# tweeq-FB_Breadboard_v4.net
KiCad netlist of a schematic drawn in EAGLE
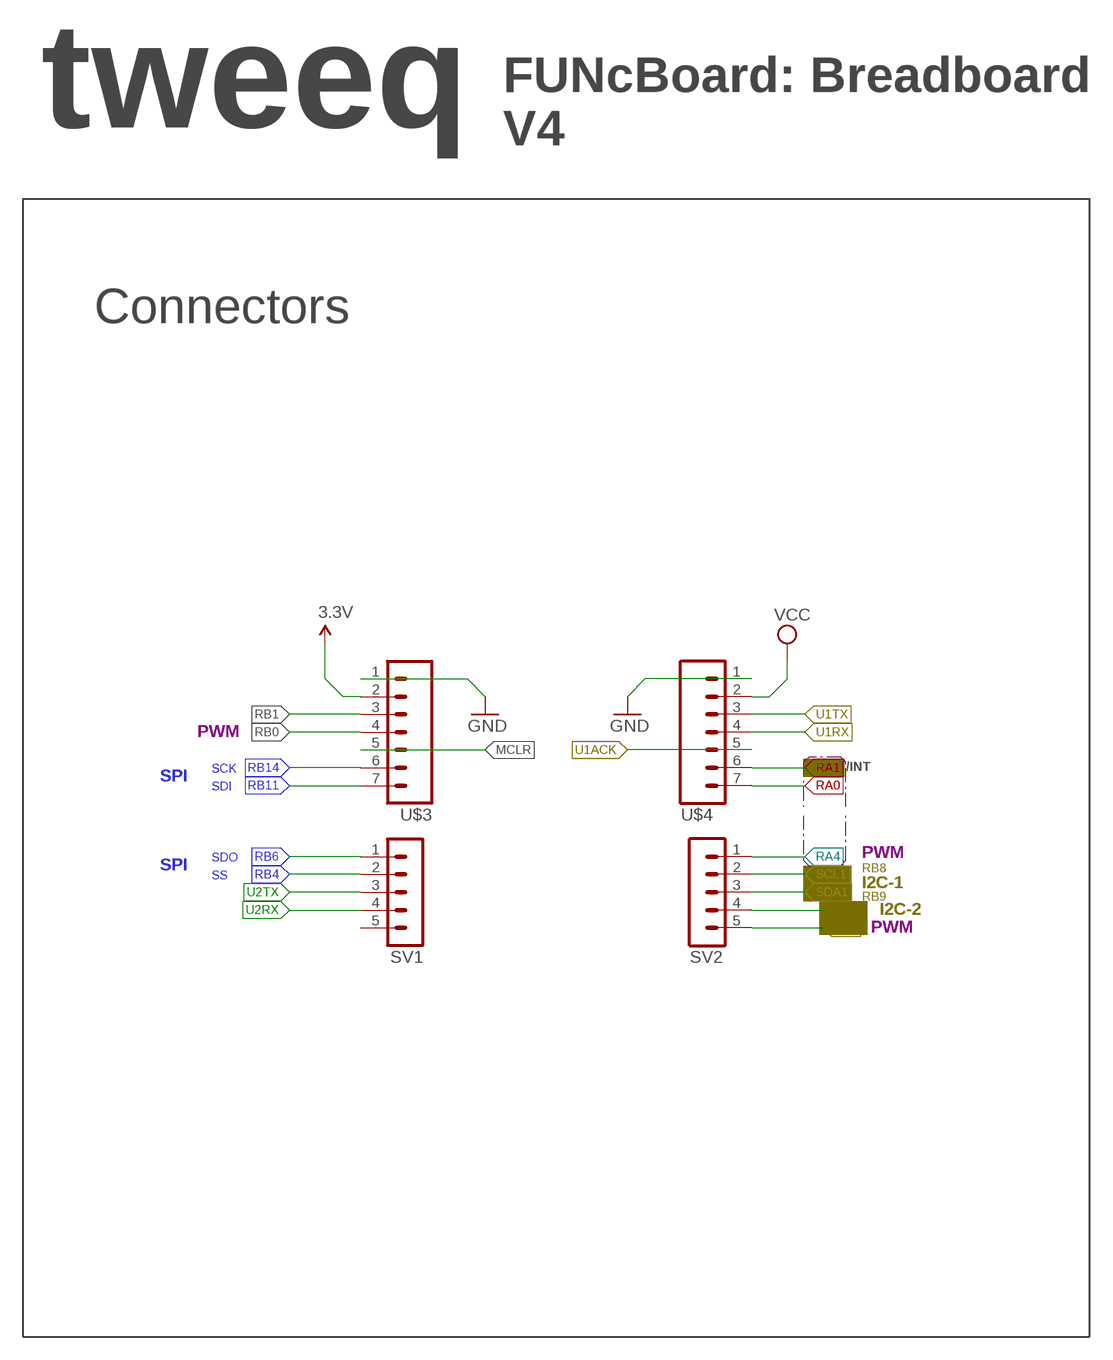
[diagram p0: schematic, sheet 1, part 1 of 2]
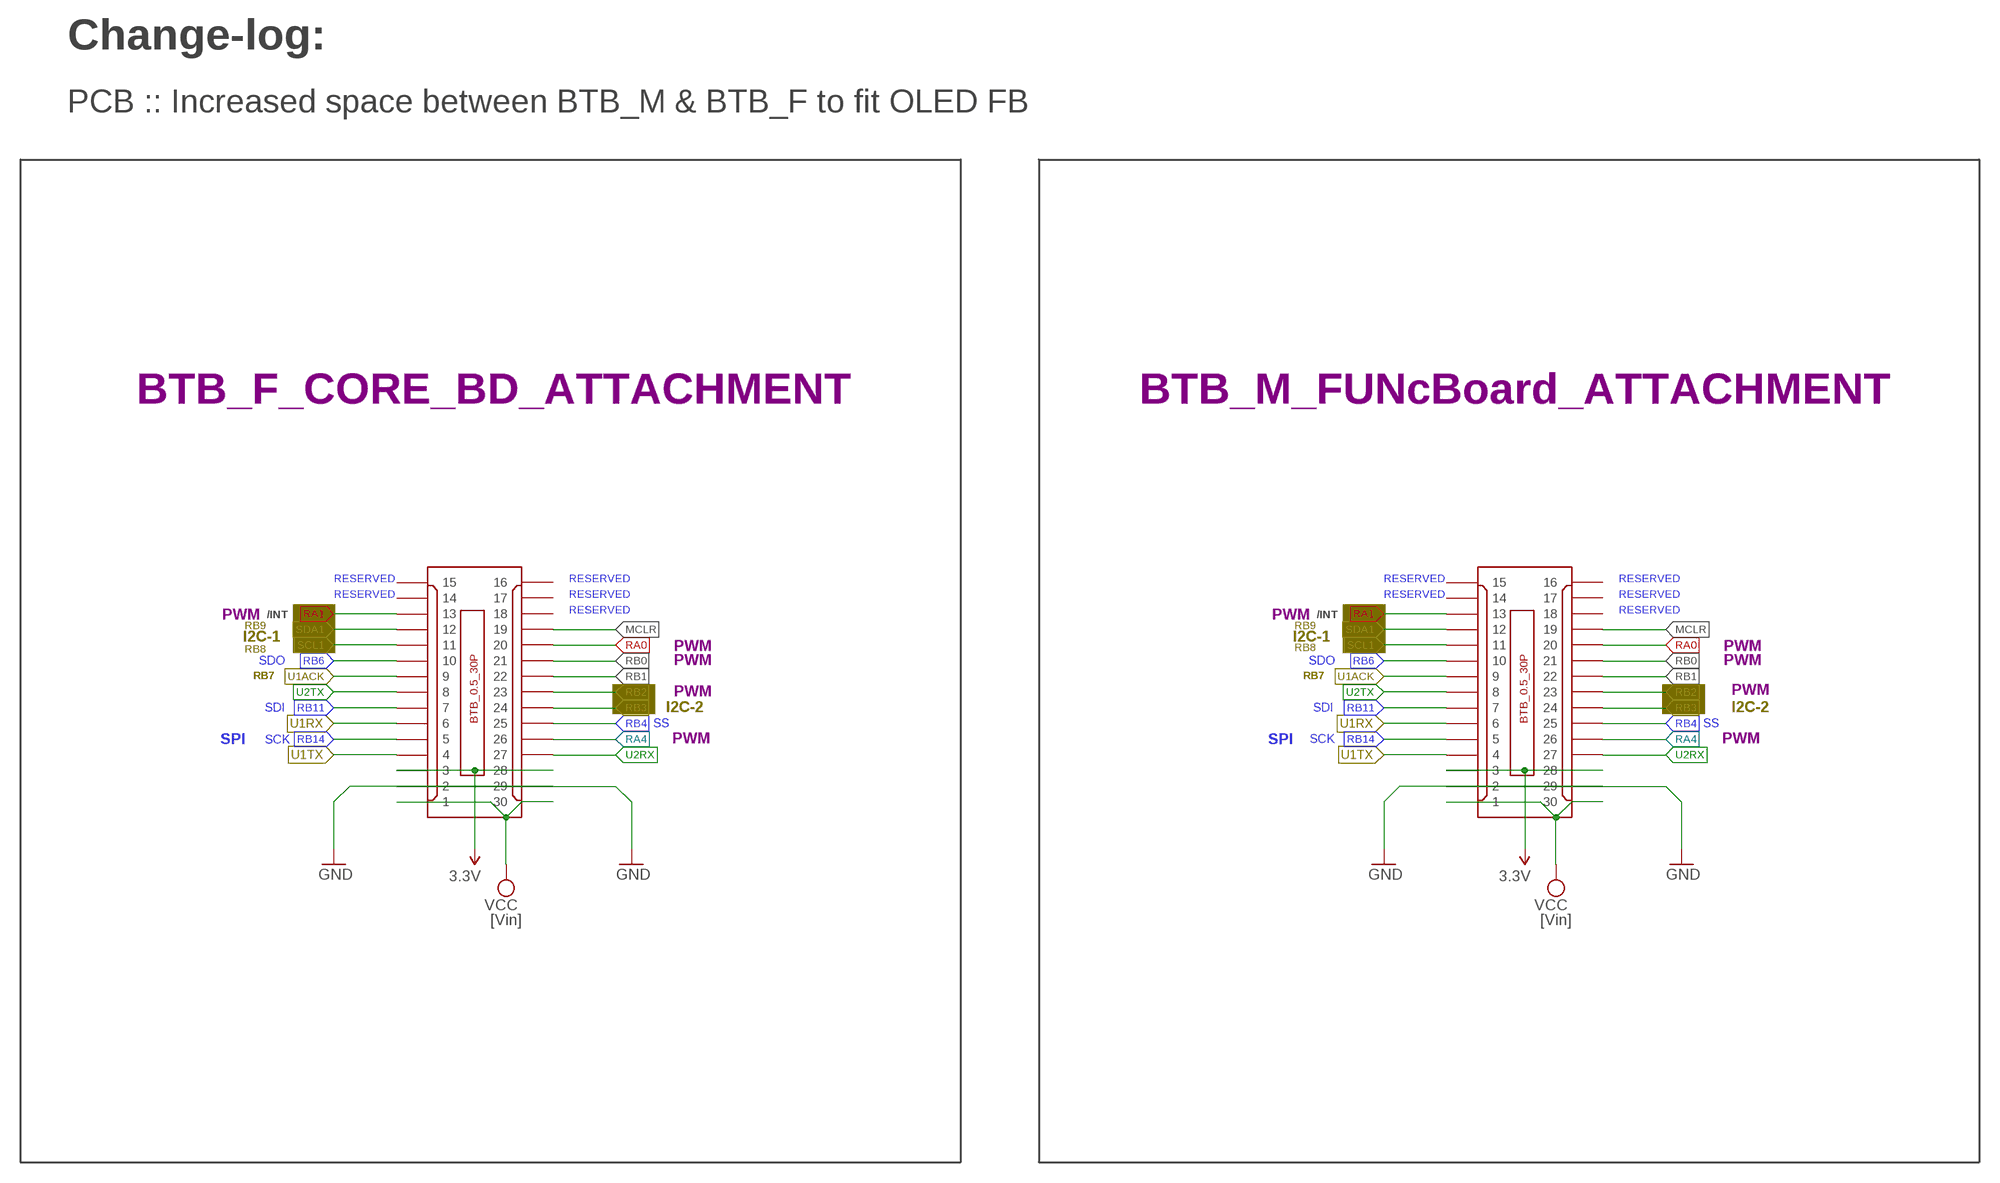
[diagram p1: schematic, sheet 1, part 2 of 2]

(export (version "E")
  (design (tool "Eeschema 10.0.6"))
  (components
    (comp (ref "SV1")
      (value "M05-1NOSILK")
      (footprint "eagle-import:1X05_NOSILK")
      (libsource (lib "eagle-import") (part "M05-1NOSILK"))
    )
    (comp (ref "SV2")
      (value "M05-1NOSILK")
      (footprint "eagle-import:1X05_NOSILK")
      (libsource (lib "eagle-import") (part "M05-1NOSILK"))
    )
    (comp (ref "U$1")
      (value "BTB_CONN_30P/M")
      (footprint "eagle-import:BTB0.5-30M-3.0G")
      (libsource (lib "eagle-import") (part "BTB_CONN_30P/M"))
    )
    (comp (ref "U$2")
      (value "BTB_CONN_30P/F")
      (footprint "eagle-import:BTB0.5-30F-3.0G")
      (libsource (lib "eagle-import") (part "BTB_CONN_30P/F"))
    )
    (comp (ref "U$3")
      (value "M07NOSILK")
      (footprint "eagle-import:1X07_NOSILK")
      (libsource (lib "eagle-import") (part "M07NOSILK"))
    )
    (comp (ref "U$4")
      (value "M07NOSILK")
      (footprint "eagle-import:1X07_NOSILK")
      (libsource (lib "eagle-import") (part "M07NOSILK"))
    )
  )
  (nets
    (net (code "1") (name "3.3V") (class "Default")
      (node (ref "U$1") (pin "28") (pinfunction "28_28") (pintype "bidirectional"))
      (node (ref "U$1") (pin "3") (pinfunction "3_3") (pintype "bidirectional"))
      (node (ref "U$2") (pin "28") (pinfunction "28_28") (pintype "bidirectional"))
      (node (ref "U$2") (pin "3") (pinfunction "3_3") (pintype "bidirectional"))
      (node (ref "U$3") (pin "2") (pinfunction "2_2") (pintype "passive"))
    )
    (net (code "2") (name "GND") (class "Default")
      (node (ref "U$1") (pin "2") (pinfunction "2_2") (pintype "bidirectional"))
      (node (ref "U$1") (pin "29") (pinfunction "29_29") (pintype "bidirectional"))
      (node (ref "U$2") (pin "2") (pinfunction "2_2") (pintype "bidirectional"))
      (node (ref "U$2") (pin "29") (pinfunction "29_29") (pintype "bidirectional"))
      (node (ref "U$3") (pin "1") (pinfunction "1_1") (pintype "passive"))
      (node (ref "U$4") (pin "1") (pinfunction "1_1") (pintype "passive"))
    )
    (net (code "3") (name "MCLR") (class "Default")
      (node (ref "U$1") (pin "19") (pinfunction "19_19") (pintype "bidirectional"))
      (node (ref "U$2") (pin "19") (pinfunction "19_19") (pintype "bidirectional"))
      (node (ref "U$3") (pin "5") (pinfunction "5_5") (pintype "passive"))
    )
    (net (code "4") (name "RA0") (class "Default")
      (node (ref "U$1") (pin "20") (pinfunction "20_20") (pintype "bidirectional"))
      (node (ref "U$2") (pin "20") (pinfunction "20_20") (pintype "bidirectional"))
      (node (ref "U$4") (pin "7") (pinfunction "7_7") (pintype "passive"))
    )
    (net (code "5") (name "RA1") (class "Default")
      (node (ref "U$1") (pin "13") (pinfunction "13_13") (pintype "bidirectional"))
      (node (ref "U$2") (pin "13") (pinfunction "13_13") (pintype "bidirectional"))
      (node (ref "U$4") (pin "6") (pinfunction "6_6") (pintype "passive"))
    )
    (net (code "6") (name "RA4") (class "Default")
      (node (ref "SV2") (pin "1") (pinfunction "1_1") (pintype "passive"))
      (node (ref "U$1") (pin "26") (pinfunction "26_26") (pintype "bidirectional"))
      (node (ref "U$2") (pin "26") (pinfunction "26_26") (pintype "bidirectional"))
    )
    (net (code "7") (name "RB0") (class "Default")
      (node (ref "U$1") (pin "21") (pinfunction "21_21") (pintype "bidirectional"))
      (node (ref "U$2") (pin "21") (pinfunction "21_21") (pintype "bidirectional"))
      (node (ref "U$3") (pin "4") (pinfunction "4_4") (pintype "passive"))
    )
    (net (code "8") (name "RB1") (class "Default")
      (node (ref "U$1") (pin "22") (pinfunction "22_22") (pintype "bidirectional"))
      (node (ref "U$2") (pin "22") (pinfunction "22_22") (pintype "bidirectional"))
      (node (ref "U$3") (pin "3") (pinfunction "3_3") (pintype "passive"))
    )
    (net (code "9") (name "RB2") (class "Default")
      (node (ref "SV2") (pin "5") (pinfunction "5_5") (pintype "passive"))
      (node (ref "U$1") (pin "23") (pinfunction "23_23") (pintype "bidirectional"))
      (node (ref "U$2") (pin "23") (pinfunction "23_23") (pintype "bidirectional"))
    )
    (net (code "10") (name "RB3") (class "Default")
      (node (ref "SV2") (pin "4") (pinfunction "4_4") (pintype "passive"))
      (node (ref "U$1") (pin "24") (pinfunction "24_24") (pintype "bidirectional"))
      (node (ref "U$2") (pin "24") (pinfunction "24_24") (pintype "bidirectional"))
    )
    (net (code "11") (name "RB4") (class "Default")
      (node (ref "SV1") (pin "2") (pinfunction "2_2") (pintype "passive"))
      (node (ref "U$1") (pin "25") (pinfunction "25_25") (pintype "bidirectional"))
      (node (ref "U$2") (pin "25") (pinfunction "25_25") (pintype "bidirectional"))
    )
    (net (code "12") (name "RB6") (class "Default")
      (node (ref "SV1") (pin "1") (pinfunction "1_1") (pintype "passive"))
      (node (ref "U$1") (pin "10") (pinfunction "10_10") (pintype "bidirectional"))
      (node (ref "U$2") (pin "10") (pinfunction "10_10") (pintype "bidirectional"))
    )
    (net (code "13") (name "RB11") (class "Default")
      (node (ref "U$1") (pin "7") (pinfunction "7_7") (pintype "bidirectional"))
      (node (ref "U$2") (pin "7") (pinfunction "7_7") (pintype "bidirectional"))
      (node (ref "U$3") (pin "7") (pinfunction "7_7") (pintype "passive"))
    )
    (net (code "14") (name "RB14") (class "Default")
      (node (ref "U$1") (pin "5") (pinfunction "5_5") (pintype "bidirectional"))
      (node (ref "U$2") (pin "5") (pinfunction "5_5") (pintype "bidirectional"))
      (node (ref "U$3") (pin "6") (pinfunction "6_6") (pintype "passive"))
    )
    (net (code "15") (name "SCL1") (class "Default")
      (node (ref "SV2") (pin "2") (pinfunction "2_2") (pintype "passive"))
      (node (ref "U$1") (pin "11") (pinfunction "11_11") (pintype "bidirectional"))
      (node (ref "U$2") (pin "11") (pinfunction "11_11") (pintype "bidirectional"))
    )
    (net (code "16") (name "SDA1") (class "Default")
      (node (ref "SV2") (pin "3") (pinfunction "3_3") (pintype "passive"))
      (node (ref "U$1") (pin "12") (pinfunction "12_12") (pintype "bidirectional"))
      (node (ref "U$2") (pin "12") (pinfunction "12_12") (pintype "bidirectional"))
    )
    (net (code "17") (name "U1ACK") (class "Default")
      (node (ref "U$1") (pin "9") (pinfunction "9_9") (pintype "bidirectional"))
      (node (ref "U$2") (pin "9") (pinfunction "9_9") (pintype "bidirectional"))
      (node (ref "U$4") (pin "5") (pinfunction "5_5") (pintype "passive"))
    )
    (net (code "18") (name "U1RX") (class "Default")
      (node (ref "U$1") (pin "6") (pinfunction "6_6") (pintype "bidirectional"))
      (node (ref "U$2") (pin "6") (pinfunction "6_6") (pintype "bidirectional"))
      (node (ref "U$4") (pin "4") (pinfunction "4_4") (pintype "passive"))
    )
    (net (code "19") (name "U1TX") (class "Default")
      (node (ref "U$1") (pin "4") (pinfunction "4_4") (pintype "bidirectional"))
      (node (ref "U$2") (pin "4") (pinfunction "4_4") (pintype "bidirectional"))
      (node (ref "U$4") (pin "3") (pinfunction "3_3") (pintype "passive"))
    )
    (net (code "20") (name "U2RX") (class "Default")
      (node (ref "SV1") (pin "4") (pinfunction "4_4") (pintype "passive"))
      (node (ref "U$1") (pin "27") (pinfunction "27_27") (pintype "bidirectional"))
      (node (ref "U$2") (pin "27") (pinfunction "27_27") (pintype "bidirectional"))
    )
    (net (code "21") (name "U2TX") (class "Default")
      (node (ref "SV1") (pin "3") (pinfunction "3_3") (pintype "passive"))
      (node (ref "U$1") (pin "8") (pinfunction "8_8") (pintype "bidirectional"))
      (node (ref "U$2") (pin "8") (pinfunction "8_8") (pintype "bidirectional"))
    )
    (net (code "22") (name "VCC") (class "Default")
      (node (ref "U$1") (pin "1") (pinfunction "1_1") (pintype "bidirectional"))
      (node (ref "U$1") (pin "30") (pinfunction "30_30") (pintype "bidirectional"))
      (node (ref "U$2") (pin "1") (pinfunction "1_1") (pintype "bidirectional"))
      (node (ref "U$2") (pin "30") (pinfunction "30_30") (pintype "bidirectional"))
      (node (ref "U$4") (pin "2") (pinfunction "2_2") (pintype "passive"))
    )
    (net (code "23") (name "unconnected-(SV1-Pad5)") (class "Default")
      (node (ref "SV1") (pin "5") (pinfunction "5_5") (pintype "passive"))
    )
    (net (code "24") (name "unconnected-(U$1-Pad14)") (class "Default")
      (node (ref "U$1") (pin "14") (pinfunction "14_14") (pintype "bidirectional"))
    )
    (net (code "25") (name "unconnected-(U$1-Pad15)") (class "Default")
      (node (ref "U$1") (pin "15") (pinfunction "15_15") (pintype "bidirectional"))
    )
    (net (code "26") (name "unconnected-(U$1-Pad16)") (class "Default")
      (node (ref "U$1") (pin "16") (pinfunction "16_16") (pintype "bidirectional"))
    )
    (net (code "27") (name "unconnected-(U$1-Pad17)") (class "Default")
      (node (ref "U$1") (pin "17") (pinfunction "17_17") (pintype "bidirectional"))
    )
    (net (code "28") (name "unconnected-(U$1-Pad18)") (class "Default")
      (node (ref "U$1") (pin "18") (pinfunction "18_18") (pintype "bidirectional"))
    )
    (net (code "29") (name "unconnected-(U$2-Pad14)") (class "Default")
      (node (ref "U$2") (pin "14") (pinfunction "14_14") (pintype "bidirectional"))
    )
    (net (code "30") (name "unconnected-(U$2-Pad15)") (class "Default")
      (node (ref "U$2") (pin "15") (pinfunction "15_15") (pintype "bidirectional"))
    )
    (net (code "31") (name "unconnected-(U$2-Pad16)") (class "Default")
      (node (ref "U$2") (pin "16") (pinfunction "16_16") (pintype "bidirectional"))
    )
    (net (code "32") (name "unconnected-(U$2-Pad17)") (class "Default")
      (node (ref "U$2") (pin "17") (pinfunction "17_17") (pintype "bidirectional"))
    )
    (net (code "33") (name "unconnected-(U$2-Pad18)") (class "Default")
      (node (ref "U$2") (pin "18") (pinfunction "18_18") (pintype "bidirectional"))
    )
  )
)
